# emu.net
KiCad netlist of a schematic drawn in EAGLE
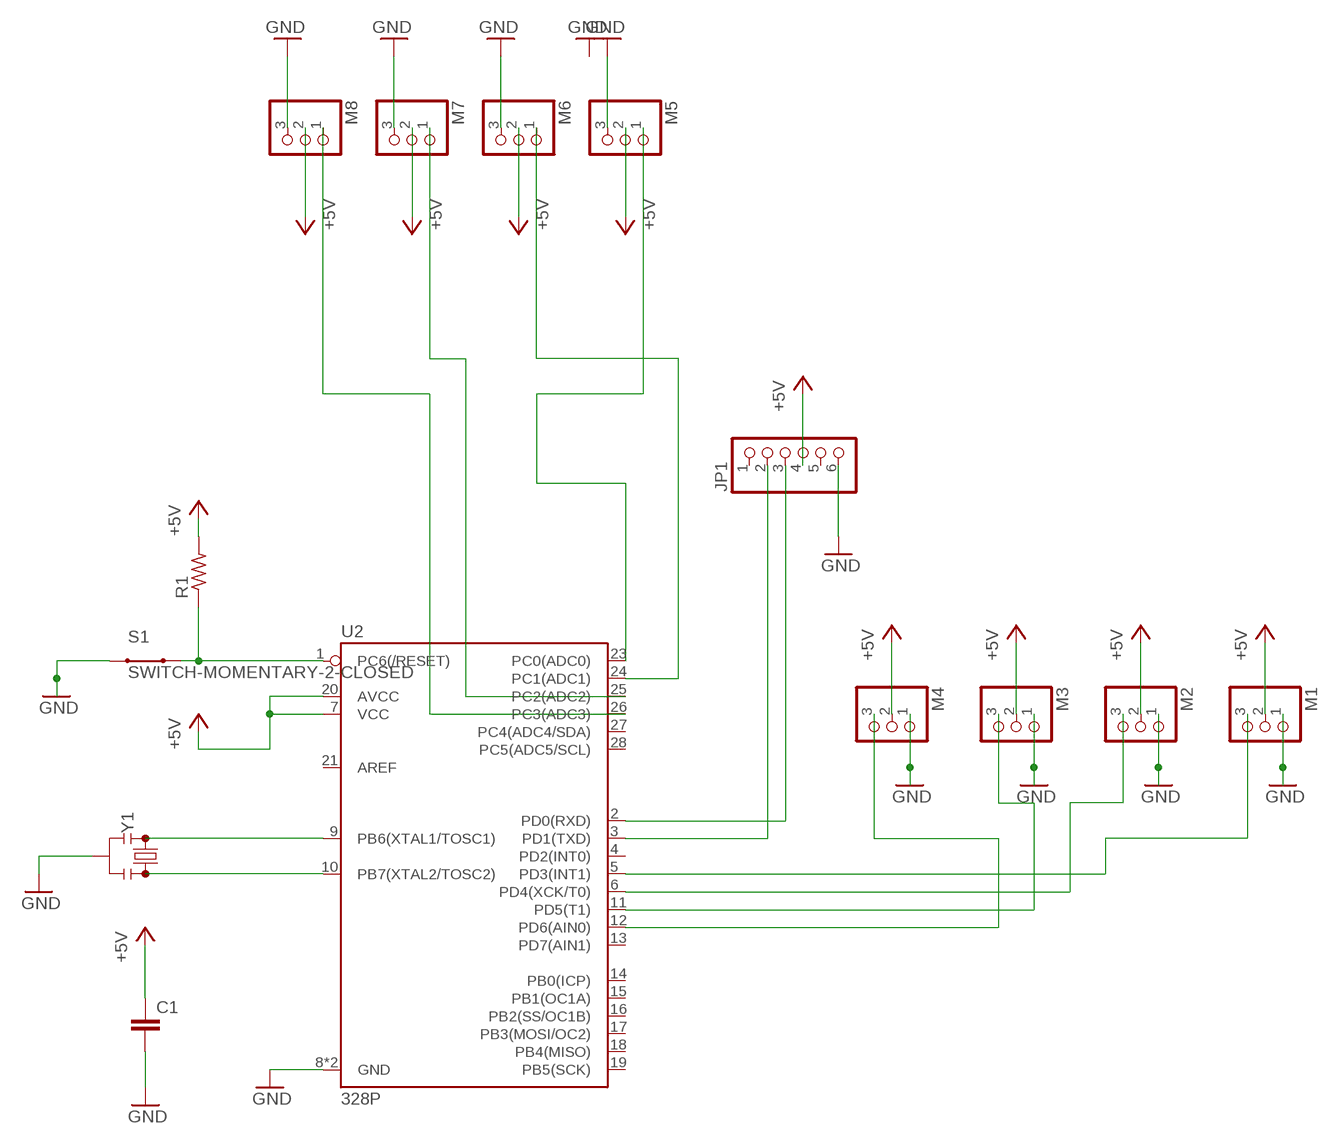
[diagram p0: schematic, sheet 1]

(export (version "E")
  (design (tool "Eeschema 10.0.6"))
  (components
    (comp (ref "C1")
      (value "C2.5/4")
      (footprint "eagle-import:C2.5-4")
      (libsource (lib "eagle-import") (part "C2.5/4"))
    )
    (comp (ref "JP1")
      (value "PINHD-1X6")
      (footprint "eagle-import:1X06")
      (libsource (lib "eagle-import") (part "PINHD-1X6"))
    )
    (comp (ref "M1")
      (value "PINHD-1X3")
      (footprint "eagle-import:1X03")
      (libsource (lib "eagle-import") (part "PINHD-1X3"))
    )
    (comp (ref "M2")
      (value "PINHD-1X3")
      (footprint "eagle-import:1X03")
      (libsource (lib "eagle-import") (part "PINHD-1X3"))
    )
    (comp (ref "M3")
      (value "PINHD-1X3")
      (footprint "eagle-import:1X03")
      (libsource (lib "eagle-import") (part "PINHD-1X3"))
    )
    (comp (ref "M4")
      (value "PINHD-1X3")
      (footprint "eagle-import:1X03")
      (libsource (lib "eagle-import") (part "PINHD-1X3"))
    )
    (comp (ref "M5")
      (value "PINHD-1X3")
      (footprint "eagle-import:1X03")
      (libsource (lib "eagle-import") (part "PINHD-1X3"))
    )
    (comp (ref "M6")
      (value "PINHD-1X3")
      (footprint "eagle-import:1X03")
      (libsource (lib "eagle-import") (part "PINHD-1X3"))
    )
    (comp (ref "M7")
      (value "PINHD-1X3")
      (footprint "eagle-import:1X03")
      (libsource (lib "eagle-import") (part "PINHD-1X3"))
    )
    (comp (ref "M8")
      (value "PINHD-1X3")
      (footprint "eagle-import:1X03")
      (libsource (lib "eagle-import") (part "PINHD-1X3"))
    )
    (comp (ref "R1")
      (value "R-US_0204/7")
      (footprint "eagle-import:0204_7")
      (libsource (lib "eagle-import") (part "R-US_0204/7"))
    )
    (comp (ref "S1")
      (value "SWITCH-MOMENTARY-2-CLOSED")
      (footprint "eagle-import:TACTILE-PTH-12MM")
      (libsource (lib "eagle-import") (part "SWITCH-MOMENTARY-2-CLOSED"))
    )
    (comp (ref "U2")
      (value "328P")
      (footprint "eagle-import:DIP28")
      (libsource (lib "eagle-import") (part "ATMEGA328P_PDIP"))
    )
    (comp (ref "Y1")
      (value "RESONATORPTH-7.6X3.8")
      (footprint "eagle-import:RESONATOR-PTH-7.6X3.8")
      (libsource (lib "eagle-import") (part "RESONATORPTH-7.6X3.8"))
    )
  )
  (nets
    (net (code "1") (name "+5V") (class "Default")
      (node (ref "C1") (pin "1") (pinfunction "1_1") (pintype "passive"))
      (node (ref "JP1") (pin "4") (pinfunction "4_4") (pintype "passive"))
      (node (ref "M1") (pin "2") (pinfunction "2_2") (pintype "passive"))
      (node (ref "M2") (pin "2") (pinfunction "2_2") (pintype "passive"))
      (node (ref "M3") (pin "2") (pinfunction "2_2") (pintype "passive"))
      (node (ref "M4") (pin "2") (pinfunction "2_2") (pintype "passive"))
      (node (ref "M5") (pin "2") (pinfunction "2_2") (pintype "passive"))
      (node (ref "M6") (pin "2") (pinfunction "2_2") (pintype "passive"))
      (node (ref "M7") (pin "2") (pinfunction "2_2") (pintype "passive"))
      (node (ref "M8") (pin "2") (pinfunction "2_2") (pintype "passive"))
      (node (ref "R1") (pin "2") (pinfunction "2_2") (pintype "passive"))
      (node (ref "U2") (pin "20") (pinfunction "AVCC_20") (pintype "bidirectional"))
      (node (ref "U2") (pin "7") (pinfunction "VCC_7") (pintype "bidirectional"))
    )
    (net (code "2") (name "GND") (class "Default")
      (node (ref "C1") (pin "2") (pinfunction "2_2") (pintype "passive"))
      (node (ref "JP1") (pin "6") (pinfunction "6_6") (pintype "passive"))
      (node (ref "M1") (pin "1") (pinfunction "1_1") (pintype "passive"))
      (node (ref "M2") (pin "1") (pinfunction "1_1") (pintype "passive"))
      (node (ref "M3") (pin "1") (pinfunction "1_1") (pintype "passive"))
      (node (ref "M4") (pin "1") (pinfunction "1_1") (pintype "passive"))
      (node (ref "M5") (pin "3") (pinfunction "3_3") (pintype "passive"))
      (node (ref "M6") (pin "3") (pinfunction "3_3") (pintype "passive"))
      (node (ref "M7") (pin "3") (pinfunction "3_3") (pintype "passive"))
      (node (ref "M8") (pin "3") (pinfunction "3_3") (pintype "passive"))
      (node (ref "S1") (pin "1") (pinfunction "1_1") (pintype "passive"))
      (node (ref "U2") (pin "22") (pinfunction "GND_22") (pintype "bidirectional"))
      (node (ref "U2") (pin "8") (pinfunction "GND_8") (pintype "bidirectional"))
      (node (ref "Y1") (pin "2") (pinfunction "2_2") (pintype "passive"))
    )
    (net (code "3") (name "Net-(S1-2)") (class "Default")
      (node (ref "R1") (pin "1") (pinfunction "1_1") (pintype "passive"))
      (node (ref "S1") (pin "3") (pinfunction "2_3") (pintype "passive"))
      (node (ref "U2") (pin "1") (pinfunction "PC6(/RESET)_1") (pintype "bidirectional"))
    )
    (net (code "4") (name "Net-(U2-PB6(XTAL1{slash}TOSC1))") (class "Default")
      (node (ref "U2") (pin "9") (pinfunction "PB6(XTAL1/TOSC1)_9") (pintype "bidirectional"))
      (node (ref "Y1") (pin "1") (pinfunction "1_1") (pintype "passive"))
    )
    (net (code "5") (name "Net-(U2-PB7(XTAL2{slash}TOSC2))") (class "Default")
      (node (ref "U2") (pin "10") (pinfunction "PB7(XTAL2/TOSC2)_10") (pintype "bidirectional"))
      (node (ref "Y1") (pin "3") (pinfunction "3_3") (pintype "passive"))
    )
    (net (code "6") (name "Net-(U2-PC0(ADC0))") (class "Default")
      (node (ref "M5") (pin "1") (pinfunction "1_1") (pintype "passive"))
      (node (ref "U2") (pin "23") (pinfunction "PC0(ADC0)_23") (pintype "bidirectional"))
    )
    (net (code "7") (name "Net-(U2-PC1(ADC1))") (class "Default")
      (node (ref "M6") (pin "1") (pinfunction "1_1") (pintype "passive"))
      (node (ref "U2") (pin "24") (pinfunction "PC1(ADC1)_24") (pintype "bidirectional"))
    )
    (net (code "8") (name "Net-(U2-PC2(ADC2))") (class "Default")
      (node (ref "M7") (pin "1") (pinfunction "1_1") (pintype "passive"))
      (node (ref "U2") (pin "25") (pinfunction "PC2(ADC2)_25") (pintype "bidirectional"))
    )
    (net (code "9") (name "Net-(U2-PC3(ADC3))") (class "Default")
      (node (ref "M8") (pin "1") (pinfunction "1_1") (pintype "passive"))
      (node (ref "U2") (pin "26") (pinfunction "PC3(ADC3)_26") (pintype "bidirectional"))
    )
    (net (code "10") (name "Net-(U2-PD0(RXD))") (class "Default")
      (node (ref "JP1") (pin "3") (pinfunction "3_3") (pintype "passive"))
      (node (ref "U2") (pin "2") (pinfunction "PD0(RXD)_2") (pintype "bidirectional"))
    )
    (net (code "11") (name "Net-(U2-PD1(TXD))") (class "Default")
      (node (ref "JP1") (pin "2") (pinfunction "2_2") (pintype "passive"))
      (node (ref "U2") (pin "3") (pinfunction "PD1(TXD)_3") (pintype "bidirectional"))
    )
    (net (code "12") (name "Net-(U2-PD3(INT1))") (class "Default")
      (node (ref "M1") (pin "3") (pinfunction "3_3") (pintype "passive"))
      (node (ref "U2") (pin "5") (pinfunction "PD3(INT1)_5") (pintype "bidirectional"))
    )
    (net (code "13") (name "Net-(U2-PD4(XCK{slash}T0))") (class "Default")
      (node (ref "M2") (pin "3") (pinfunction "3_3") (pintype "passive"))
      (node (ref "U2") (pin "6") (pinfunction "PD4(XCK/T0)_6") (pintype "bidirectional"))
    )
    (net (code "14") (name "Net-(U2-PD5(T1))") (class "Default")
      (node (ref "M3") (pin "3") (pinfunction "3_3") (pintype "passive"))
      (node (ref "U2") (pin "11") (pinfunction "PD5(T1)_11") (pintype "bidirectional"))
    )
    (net (code "15") (name "Net-(U2-PD6(AIN0))") (class "Default")
      (node (ref "M4") (pin "3") (pinfunction "3_3") (pintype "passive"))
      (node (ref "U2") (pin "12") (pinfunction "PD6(AIN0)_12") (pintype "bidirectional"))
    )
    (net (code "16") (name "unconnected-(JP1-Pad1)") (class "Default")
      (node (ref "JP1") (pin "1") (pinfunction "1_1") (pintype "passive"))
    )
    (net (code "17") (name "unconnected-(JP1-Pad5)") (class "Default")
      (node (ref "JP1") (pin "5") (pinfunction "5_5") (pintype "passive"))
    )
    (net (code "18") (name "unconnected-(U2-AREF-Pad21)") (class "Default")
      (node (ref "U2") (pin "21") (pinfunction "AREF_21") (pintype "bidirectional"))
    )
    (net (code "19") (name "unconnected-(U2-PB0(ICP)-Pad14)") (class "Default")
      (node (ref "U2") (pin "14") (pinfunction "PB0(ICP)_14") (pintype "bidirectional"))
    )
    (net (code "20") (name "unconnected-(U2-PB1(OC1A)-Pad15)") (class "Default")
      (node (ref "U2") (pin "15") (pinfunction "PB1(OC1A)_15") (pintype "bidirectional"))
    )
    (net (code "21") (name "unconnected-(U2-PB2(SS{slash}OC1B)-Pad16)") (class "Default")
      (node (ref "U2") (pin "16") (pinfunction "PB2(SS/OC1B)_16") (pintype "bidirectional"))
    )
    (net (code "22") (name "unconnected-(U2-PB3(MOSI{slash}OC2)-Pad17)") (class "Default")
      (node (ref "U2") (pin "17") (pinfunction "PB3(MOSI/OC2)_17") (pintype "bidirectional"))
    )
    (net (code "23") (name "unconnected-(U2-PB4(MISO)-Pad18)") (class "Default")
      (node (ref "U2") (pin "18") (pinfunction "PB4(MISO)_18") (pintype "bidirectional"))
    )
    (net (code "24") (name "unconnected-(U2-PB5(SCK)-Pad19)") (class "Default")
      (node (ref "U2") (pin "19") (pinfunction "PB5(SCK)_19") (pintype "bidirectional"))
    )
    (net (code "25") (name "unconnected-(U2-PC4(ADC4{slash}SDA)-Pad27)") (class "Default")
      (node (ref "U2") (pin "27") (pinfunction "PC4(ADC4/SDA)_27") (pintype "bidirectional"))
    )
    (net (code "26") (name "unconnected-(U2-PC5(ADC5{slash}SCL)-Pad28)") (class "Default")
      (node (ref "U2") (pin "28") (pinfunction "PC5(ADC5/SCL)_28") (pintype "bidirectional"))
    )
    (net (code "27") (name "unconnected-(U2-PD2(INT0)-Pad4)") (class "Default")
      (node (ref "U2") (pin "4") (pinfunction "PD2(INT0)_4") (pintype "bidirectional"))
    )
    (net (code "28") (name "unconnected-(U2-PD7(AIN1)-Pad13)") (class "Default")
      (node (ref "U2") (pin "13") (pinfunction "PD7(AIN1)_13") (pintype "bidirectional"))
    )
  )
)
